# LDO.net
KiCad netlist of a schematic drawn in Altium Designer
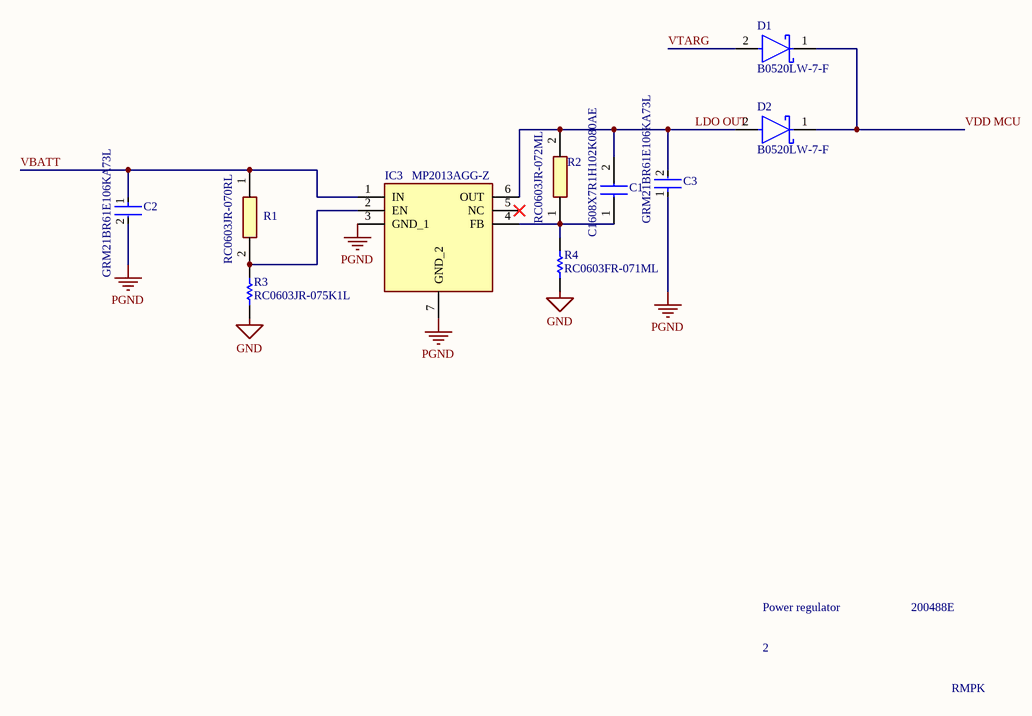
[diagram p0: LDO.SchDoc]

(export (version "E")
  (design (tool "Eeschema 10.0.6"))
  (components
    (comp (ref "C1")
      (value "C1608X7R1H102K080AE")
      (footprint "SamacSys:CAPC1608X80N")
      (description "Capacitor")
      (fields (field (name "MOUSER PART NUMBER") "810-C1608X7R1H102KAE"))
      (libsource (lib "*") (part "C1608X7R1H102K080AE"))
    )
    (comp (ref "C2")
      (value "GRM21BR61E106KA73L")
      (footprint "FP-GRM21B-0_15-IPC_C")
      (description "Chip Multilayer Ceramic Capacitors for General Purpose, 0805, 10uF, X5R, 15%, 10%, 25V")
      (fields (field (name "VOLTAGE") "25V") (field (name "TOLERANCE") "10%"))
      (libsource (lib "Altium Content Vault") (part "b4654b650e69147ec39a6b967a45e02"))
    )
    (comp (ref "C3")
      (value "GRM21BR61E106KA73L")
      (footprint "FP-GRM21B-0_15-IPC_C")
      (description "Chip Multilayer Ceramic Capacitors for General Purpose, 0805, 10uF, X5R, 15%, 10%, 25V")
      (fields (field (name "VOLTAGE") "25V") (field (name "TOLERANCE") "10%"))
      (libsource (lib "Altium Content Vault") (part "b4654b650e69147ec39a6b967a45e02"))
    )
    (comp (ref "D1")
      (value "B0520LW-7-F")
      (footprint "FP-SOD123-MFG")
      (description "DIODE SCHOTTKY 20V 500MA SOD123")
      (fields
        (field (name "OCTOPART") "https://octopart.com/b0520lw-7-f-diodes+inc.-325707")
        (field (name "MANUFACTURER") "Diodes Inc.")
      )
      (libsource (lib "Altium Content Vault") (part "1d6ec82d83fb6aee721767c19dac4b9"))
    )
    (comp (ref "D2")
      (value "B0520LW-7-F")
      (footprint "FP-SOD123-MFG")
      (description "DIODE SCHOTTKY 20V 500MA SOD123")
      (fields
        (field (name "OCTOPART") "https://octopart.com/b0520lw-7-f-diodes+inc.-325707")
        (field (name "MANUFACTURER") "Diodes Inc.")
      )
      (libsource (lib "Altium Content Vault") (part "1d6ec82d83fb6aee721767c19dac4b9"))
    )
    (comp (ref "IC3")
      (value "MP2013AGG-Z")
      (footprint "SamacSys:SON65P200X200X100-7N-D")
      (description "Integrated Circuit")
      (fields (field (name "MOUSER PART NUMBER") "946-MP2013AGG-Z"))
      (libsource (lib "*") (part "MP2013AGG-Z"))
    )
    (comp (ref "R1")
      (value "RC0603JR-070RL")
      (footprint "SamacSys:RESC1608X55N")
      (description "Resistor")
      (fields (field (name "MOUSER PART NUMBER") "603-RC0603JR-070RL"))
      (libsource (lib "*") (part "RC0603JR-070RL"))
    )
    (comp (ref "R2")
      (value "RC0603JR-072ML")
      (footprint "SamacSys:RESC1608X55N")
      (description "Resistor")
      (libsource (lib "*") (part "RC0603JR-072ML"))
    )
    (comp (ref "R3")
      (value "RC0603JR-075K1L")
      (footprint "RESC1608X55X25LL10T15")
      (description "Chip Resistor, 5.1 KOhm, +/- 5%, 0.1 W, -55 to 155 degC, 0603 (1608 Metric), RoHS, Tape and Reel")
      (fields (field (name "TOLERANCE") "5%") (field (name "MANUFACTURER") "Yageo"))
      (libsource (lib "Altium Content Vault") (part "RES-2"))
    )
    (comp (ref "R4")
      (value "RC0603FR-071ML")
      (footprint "RESC1608X55X25LL10T15")
      (description "Chip Resistor, 1 MOhm, +/- 1%, 100 mW, -55 to 155 degC, 0603 (1608 Metric), RoHS, Tape and Reel")
      (fields (field (name "TOLERANCE") "20%"))
      (libsource (lib "Altium Content Vault") (part "RES-2"))
    )
  )
  (nets
    (net (code "1") (name "/LDO OUT") (class "Default")
      (node (ref "C1") (pin "2") (pinfunction "2_2") (pintype "passive"))
      (node (ref "C3") (pin "2") (pinfunction "2_2") (pintype "passive"))
      (node (ref "D2") (pin "2") (pinfunction "A_2") (pintype "passive"))
      (node (ref "IC3") (pin "6") (pinfunction "OUT_6") (pintype "passive"))
      (node (ref "R2") (pin "2") (pinfunction "2_2") (pintype "passive"))
    )
    (net (code "2") (name "/VBATT") (class "Default")
      (node (ref "C2") (pin "1") (pinfunction "1_1") (pintype "passive"))
      (node (ref "IC3") (pin "1") (pinfunction "IN_1") (pintype "passive"))
      (node (ref "R1") (pin "1") (pinfunction "1_1") (pintype "passive"))
    )
    (net (code "3") (name "/VDD MCU") (class "Default")
      (node (ref "D1") (pin "1") (pinfunction "C_1") (pintype "passive"))
      (node (ref "D2") (pin "1") (pinfunction "C_1") (pintype "passive"))
    )
    (net (code "4") (name "/VTARG") (class "Default")
      (node (ref "D1") (pin "2") (pinfunction "A_2") (pintype "passive"))
    )
    (net (code "5") (name "GND") (class "Default")
      (node (ref "R3") (pin "1") (pinfunction "1_1") (pintype "passive"))
      (node (ref "R4") (pin "1") (pinfunction "1_1") (pintype "passive"))
    )
    (net (code "6") (name "Net-(IC3-EN)") (class "Default")
      (node (ref "IC3") (pin "2") (pinfunction "EN_2") (pintype "passive"))
      (node (ref "R1") (pin "2") (pinfunction "2_2") (pintype "passive"))
      (node (ref "R3") (pin "2") (pinfunction "2_2") (pintype "passive"))
    )
    (net (code "7") (name "Net-(IC3-FB)") (class "Default")
      (node (ref "C1") (pin "1") (pinfunction "1_1") (pintype "passive"))
      (node (ref "IC3") (pin "4") (pinfunction "FB_4") (pintype "passive"))
      (node (ref "R2") (pin "1") (pinfunction "1_1") (pintype "passive"))
      (node (ref "R4") (pin "2") (pinfunction "2_2") (pintype "passive"))
    )
    (net (code "8") (name "PGND") (class "Default")
      (node (ref "C2") (pin "2") (pinfunction "2_2") (pintype "passive"))
      (node (ref "C3") (pin "1") (pinfunction "1_1") (pintype "passive"))
      (node (ref "IC3") (pin "3") (pinfunction "GND_1_3") (pintype "passive"))
      (node (ref "IC3") (pin "7") (pinfunction "GND_2_7") (pintype "passive"))
    )
    (net (code "9") (name "unconnected-(IC3-NC-Pad5)") (class "Default")
      (node (ref "IC3") (pin "5") (pinfunction "NC_5") (pintype "passive+no_connect"))
    )
  )
)
